# DigitalConnector.net
KiCad netlist of a schematic drawn in Altium Designer
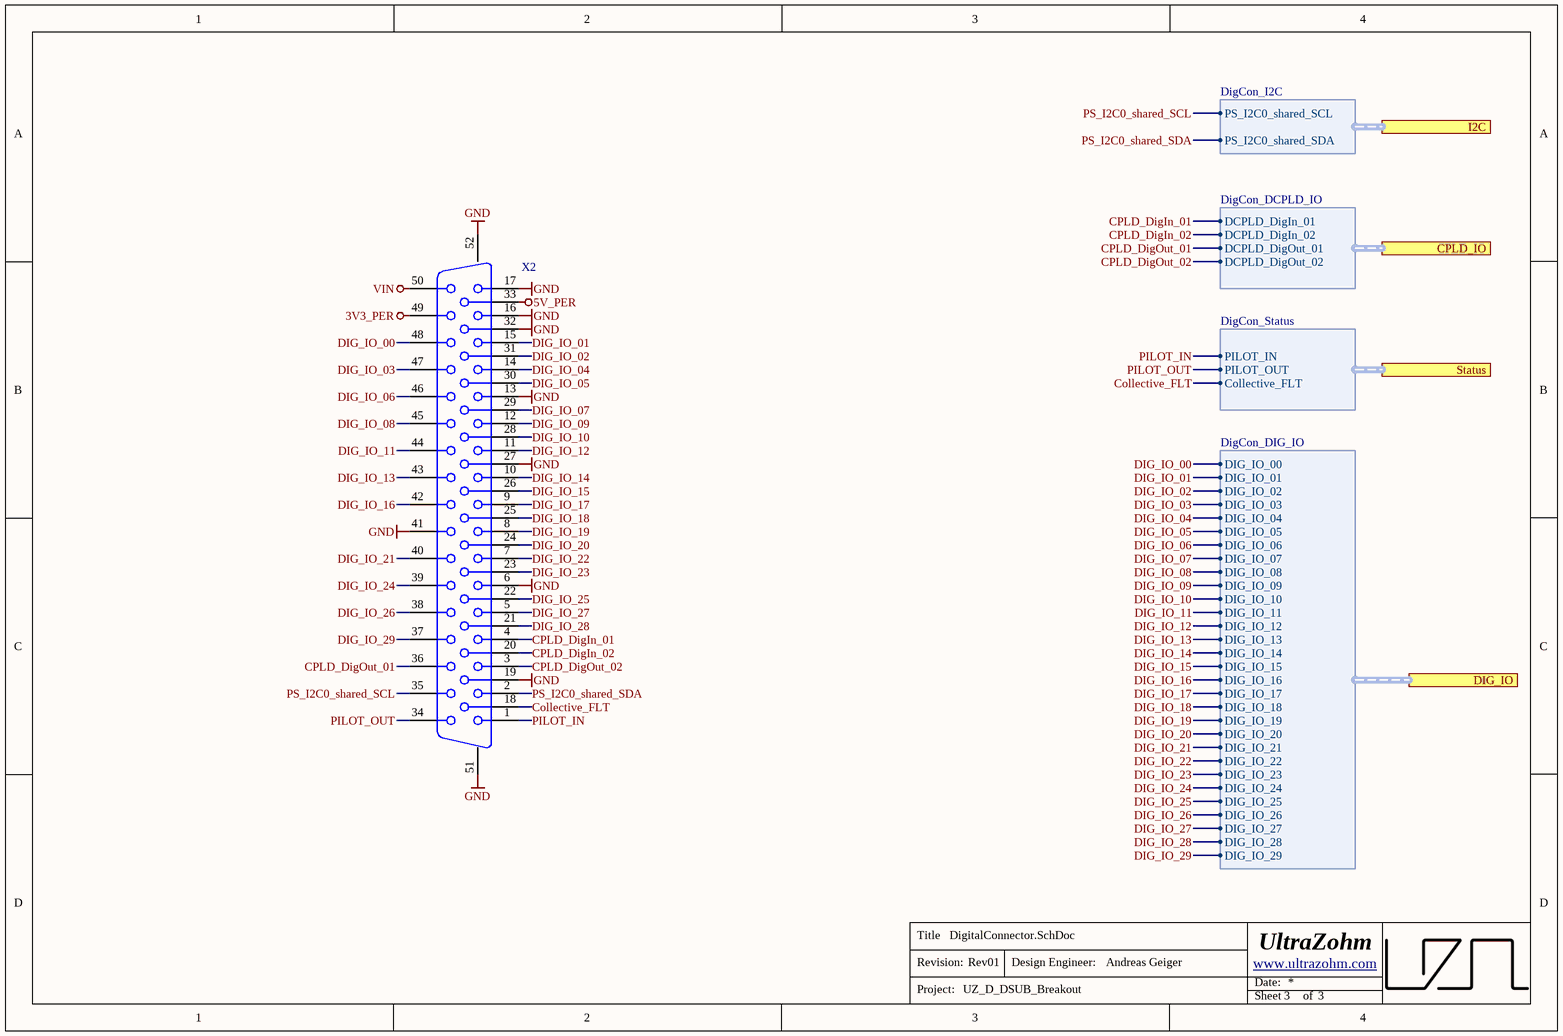
[diagram p0: DigitalConnector.SchDoc]

(export (version "E")
  (design (tool "Eeschema 10.0.6"))
  (components
    (comp (ref "X2")
      (value "~")
      (footprint "dsub50_female_164A18759X")
      (description "D-Sub Standard Connectors DSUB SOLDER PIN ANG 9.4mm")
      (fields
        (field (name "MF") "CONEC")
        (field (name "MPN") "164A18759X")
        (field (name "CREATED") "2019_10_24_AGeiger")
        (field (name "CREATED FROM") "AGeiger")
      )
      (libsource (lib "user") (part "DSUB50_female"))
    )
  )
  (nets
    (net (code "5") (name "/CPLD_DigIn_01") (class "Default")
      (node (ref "X2") (pin "4") (pinfunction "4_4") (pintype "passive"))
    )
    (net (code "6") (name "/CPLD_DigIn_02") (class "Default")
      (node (ref "X2") (pin "20") (pinfunction "20_20") (pintype "passive"))
    )
    (net (code "7") (name "/CPLD_DigOut_01") (class "Default")
      (node (ref "X2") (pin "36") (pinfunction "36_36") (pintype "passive"))
    )
    (net (code "8") (name "/CPLD_DigOut_02") (class "Default")
      (node (ref "X2") (pin "3") (pinfunction "3_3") (pintype "passive"))
    )
    (net (code "9") (name "/Collective_FLT") (class "Default")
      (node (ref "X2") (pin "18") (pinfunction "18_18") (pintype "passive"))
    )
    (net (code "10") (name "/DIG_IO_00") (class "Default")
      (node (ref "X2") (pin "48") (pinfunction "48_48") (pintype "passive"))
    )
    (net (code "11") (name "/DIG_IO_01") (class "Default")
      (node (ref "X2") (pin "15") (pinfunction "15_15") (pintype "passive"))
    )
    (net (code "12") (name "/DIG_IO_02") (class "Default")
      (node (ref "X2") (pin "31") (pinfunction "31_31") (pintype "passive"))
    )
    (net (code "13") (name "/DIG_IO_03") (class "Default")
      (node (ref "X2") (pin "47") (pinfunction "47_47") (pintype "passive"))
    )
    (net (code "14") (name "/DIG_IO_04") (class "Default")
      (node (ref "X2") (pin "14") (pinfunction "14_14") (pintype "passive"))
    )
    (net (code "15") (name "/DIG_IO_05") (class "Default")
      (node (ref "X2") (pin "30") (pinfunction "30_30") (pintype "passive"))
    )
    (net (code "16") (name "/DIG_IO_06") (class "Default")
      (node (ref "X2") (pin "46") (pinfunction "46_46") (pintype "passive"))
    )
    (net (code "17") (name "/DIG_IO_07") (class "Default")
      (node (ref "X2") (pin "29") (pinfunction "29_29") (pintype "passive"))
    )
    (net (code "18") (name "/DIG_IO_08") (class "Default")
      (node (ref "X2") (pin "45") (pinfunction "45_45") (pintype "passive"))
    )
    (net (code "19") (name "/DIG_IO_09") (class "Default")
      (node (ref "X2") (pin "12") (pinfunction "12_12") (pintype "passive"))
    )
    (net (code "20") (name "/DIG_IO_10") (class "Default")
      (node (ref "X2") (pin "28") (pinfunction "28_28") (pintype "passive"))
    )
    (net (code "21") (name "/DIG_IO_11") (class "Default")
      (node (ref "X2") (pin "44") (pinfunction "44_44") (pintype "passive"))
    )
    (net (code "22") (name "/DIG_IO_12") (class "Default")
      (node (ref "X2") (pin "11") (pinfunction "11_11") (pintype "passive"))
    )
    (net (code "23") (name "/DIG_IO_13") (class "Default")
      (node (ref "X2") (pin "43") (pinfunction "43_43") (pintype "passive"))
    )
    (net (code "24") (name "/DIG_IO_14") (class "Default")
      (node (ref "X2") (pin "10") (pinfunction "10_10") (pintype "passive"))
    )
    (net (code "25") (name "/DIG_IO_15") (class "Default")
      (node (ref "X2") (pin "26") (pinfunction "26_26") (pintype "passive"))
    )
    (net (code "26") (name "/DIG_IO_16") (class "Default")
      (node (ref "X2") (pin "42") (pinfunction "42_42") (pintype "passive"))
    )
    (net (code "27") (name "/DIG_IO_17") (class "Default")
      (node (ref "X2") (pin "9") (pinfunction "9_9") (pintype "passive"))
    )
    (net (code "28") (name "/DIG_IO_18") (class "Default")
      (node (ref "X2") (pin "25") (pinfunction "25_25") (pintype "passive"))
    )
    (net (code "29") (name "/DIG_IO_19") (class "Default")
      (node (ref "X2") (pin "8") (pinfunction "8_8") (pintype "passive"))
    )
    (net (code "30") (name "/DIG_IO_20") (class "Default")
      (node (ref "X2") (pin "24") (pinfunction "24_24") (pintype "passive"))
    )
    (net (code "31") (name "/DIG_IO_21") (class "Default")
      (node (ref "X2") (pin "40") (pinfunction "40_40") (pintype "passive"))
    )
    (net (code "32") (name "/DIG_IO_22") (class "Default")
      (node (ref "X2") (pin "7") (pinfunction "7_7") (pintype "passive"))
    )
    (net (code "33") (name "/DIG_IO_23") (class "Default")
      (node (ref "X2") (pin "23") (pinfunction "23_23") (pintype "passive"))
    )
    (net (code "34") (name "/DIG_IO_24") (class "Default")
      (node (ref "X2") (pin "39") (pinfunction "39_39") (pintype "passive"))
    )
    (net (code "35") (name "/DIG_IO_25") (class "Default")
      (node (ref "X2") (pin "22") (pinfunction "22_22") (pintype "passive"))
    )
    (net (code "36") (name "/DIG_IO_26") (class "Default")
      (node (ref "X2") (pin "38") (pinfunction "38_38") (pintype "passive"))
    )
    (net (code "37") (name "/DIG_IO_27") (class "Default")
      (node (ref "X2") (pin "5") (pinfunction "5_5") (pintype "passive"))
    )
    (net (code "38") (name "/DIG_IO_28") (class "Default")
      (node (ref "X2") (pin "21") (pinfunction "21_21") (pintype "passive"))
    )
    (net (code "39") (name "/DIG_IO_29") (class "Default")
      (node (ref "X2") (pin "37") (pinfunction "37_37") (pintype "passive"))
    )
    (net (code "40") (name "/PILOT_IN") (class "Default")
      (node (ref "X2") (pin "1") (pinfunction "1_1") (pintype "passive"))
    )
    (net (code "41") (name "/PILOT_OUT") (class "Default")
      (node (ref "X2") (pin "34") (pinfunction "34_34") (pintype "passive"))
    )
    (net (code "42") (name "/PS_I2C0_shared_SCL") (class "Default")
      (node (ref "X2") (pin "35") (pinfunction "35_35") (pintype "passive"))
    )
    (net (code "43") (name "/PS_I2C0_shared_SDA") (class "Default")
      (node (ref "X2") (pin "2") (pinfunction "2_2") (pintype "passive"))
    )
    (net (code "48") (name "3V3_PER") (class "Default")
      (node (ref "X2") (pin "49") (pinfunction "49_49") (pintype "passive"))
    )
    (net (code "49") (name "5V_PER") (class "Default")
      (node (ref "X2") (pin "33") (pinfunction "33_33") (pintype "passive"))
    )
    (net (code "50") (name "GND") (class "Default")
      (node (ref "X2") (pin "13") (pinfunction "13_13") (pintype "passive"))
      (node (ref "X2") (pin "16") (pinfunction "16_16") (pintype "passive"))
      (node (ref "X2") (pin "17") (pinfunction "17_17") (pintype "passive"))
      (node (ref "X2") (pin "19") (pinfunction "19_19") (pintype "passive"))
      (node (ref "X2") (pin "27") (pinfunction "27_27") (pintype "passive"))
      (node (ref "X2") (pin "32") (pinfunction "32_32") (pintype "passive"))
      (node (ref "X2") (pin "41") (pinfunction "41_41") (pintype "passive"))
      (node (ref "X2") (pin "51") (pinfunction "51_51") (pintype "passive"))
      (node (ref "X2") (pin "52") (pinfunction "52_52") (pintype "passive"))
      (node (ref "X2") (pin "6") (pinfunction "6_6") (pintype "passive"))
    )
    (net (code "51") (name "VIN") (class "Default")
      (node (ref "X2") (pin "50") (pinfunction "50_50") (pintype "passive"))
    )
  )
)
